# potentiometer.net
KiCad netlist of a schematic drawn in EAGLE
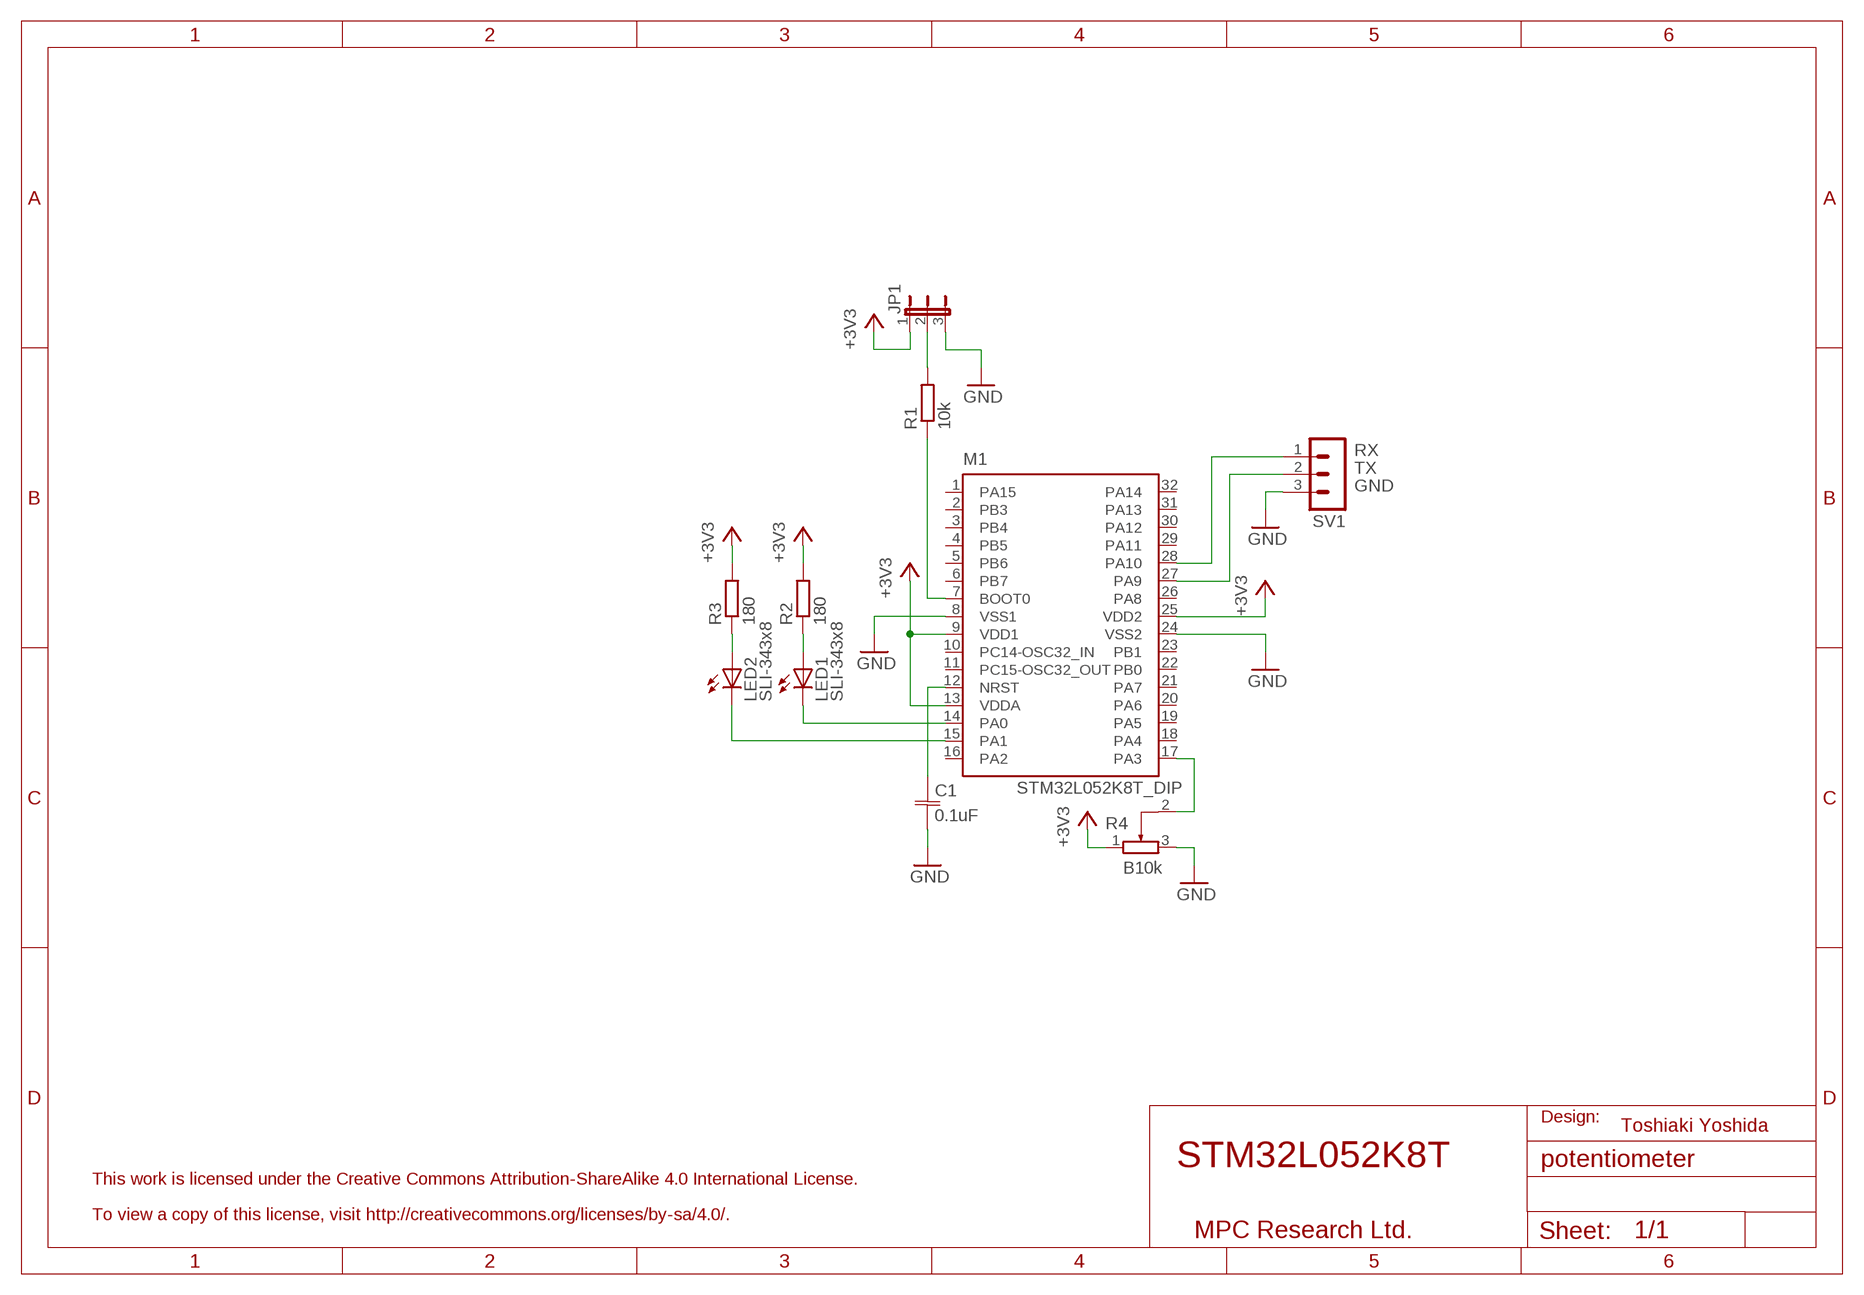
[diagram p0: schematic, sheet 1]

(export (version "E")
  (design (tool "Eeschema 10.0.6"))
  (components
    (comp (ref "C1")
      (value "0.1uF")
      (footprint "eagle-import:C050-024X044")
      (libsource (lib "eagle-import") (part "C-JIS050-024X044"))
    )
    (comp (ref "JP1")
      (value "JP2E")
      (footprint "eagle-import:JP2")
      (libsource (lib "eagle-import") (part "JP2E"))
    )
    (comp (ref "LED1")
      (value "SLI-343x8")
      (footprint "eagle-import:LED3MM")
      (libsource (lib "eagle-import") (part "LED3MM"))
    )
    (comp (ref "LED2")
      (value "SLI-343x8")
      (footprint "eagle-import:LED3MM")
      (libsource (lib "eagle-import") (part "LED3MM"))
    )
    (comp (ref "M1")
      (value "STM32L052K8T_DIP")
      (footprint "eagle-import:DIP32")
      (libsource (lib "eagle-import") (part "STM32L052K8T_DIP"))
    )
    (comp (ref "R1")
      (value "10k")
      (footprint "eagle-import:0207_2V")
      (libsource (lib "eagle-import") (part "R-EU_0207/2V"))
    )
    (comp (ref "R2")
      (value "180")
      (footprint "eagle-import:0207_2V")
      (libsource (lib "eagle-import") (part "R-EU_0207/2V"))
    )
    (comp (ref "R3")
      (value "180")
      (footprint "eagle-import:0207_2V")
      (libsource (lib "eagle-import") (part "R-EU_0207/2V"))
    )
    (comp (ref "R4")
      (value "B10k")
      (footprint "eagle-import:RK09L1140")
      (libsource (lib "eagle-import") (part "RK09L1140"))
    )
    (comp (ref "SV1")
      (value "MA03-1")
      (footprint "eagle-import:MA03-1")
      (libsource (lib "eagle-import") (part "MA03-1"))
    )
  )
  (nets
    (net (code "1") (name "+3V3") (class "Default")
      (node (ref "JP1") (pin "1") (pinfunction "1_1") (pintype "passive"))
      (node (ref "M1") (pin "13") (pinfunction "VDDA_13") (pintype "power_in"))
      (node (ref "M1") (pin "25") (pinfunction "VDD2_25") (pintype "bidirectional"))
      (node (ref "M1") (pin "9") (pinfunction "VDD1_9") (pintype "power_in"))
      (node (ref "R2") (pin "2") (pinfunction "2_2") (pintype "passive"))
      (node (ref "R3") (pin "2") (pinfunction "2_2") (pintype "passive"))
      (node (ref "R4") (pin "1") (pinfunction "1_1") (pintype "passive"))
    )
    (net (code "2") (name "GND") (class "Default")
      (node (ref "C1") (pin "2") (pinfunction "2_2") (pintype "passive"))
      (node (ref "JP1") (pin "3") (pinfunction "3_3") (pintype "passive"))
      (node (ref "M1") (pin "24") (pinfunction "VSS2_24") (pintype "power_in"))
      (node (ref "M1") (pin "8") (pinfunction "VSS1_8") (pintype "power_in"))
      (node (ref "R4") (pin "3") (pinfunction "3_3") (pintype "passive"))
      (node (ref "SV1") (pin "3") (pinfunction "3_3") (pintype "passive"))
    )
    (net (code "3") (name "Net-(JP1-Pad2)") (class "Default")
      (node (ref "JP1") (pin "2") (pinfunction "2_2") (pintype "passive"))
      (node (ref "R1") (pin "2") (pinfunction "2_2") (pintype "passive"))
    )
    (net (code "4") (name "Net-(LED1-C)") (class "Default")
      (node (ref "LED1") (pin "K") (pinfunction "C_K") (pintype "passive"))
      (node (ref "M1") (pin "14") (pinfunction "PA0_14") (pintype "bidirectional"))
    )
    (net (code "5") (name "Net-(LED1-PadA)") (class "Default")
      (node (ref "LED1") (pin "A") (pinfunction "A_A") (pintype "passive"))
      (node (ref "R2") (pin "1") (pinfunction "1_1") (pintype "passive"))
    )
    (net (code "6") (name "Net-(LED2-C)") (class "Default")
      (node (ref "LED2") (pin "K") (pinfunction "C_K") (pintype "passive"))
      (node (ref "M1") (pin "15") (pinfunction "PA1_15") (pintype "bidirectional"))
    )
    (net (code "7") (name "Net-(LED2-PadA)") (class "Default")
      (node (ref "LED2") (pin "A") (pinfunction "A_A") (pintype "passive"))
      (node (ref "R3") (pin "1") (pinfunction "1_1") (pintype "passive"))
    )
    (net (code "8") (name "Net-(M1-BOOT0)") (class "Default")
      (node (ref "M1") (pin "7") (pinfunction "BOOT0_7") (pintype "bidirectional"))
      (node (ref "R1") (pin "1") (pinfunction "1_1") (pintype "passive"))
    )
    (net (code "9") (name "Net-(M1-NRST)") (class "Default")
      (node (ref "C1") (pin "1") (pinfunction "1_1") (pintype "passive"))
      (node (ref "M1") (pin "12") (pinfunction "NRST_12") (pintype "bidirectional"))
    )
    (net (code "10") (name "Net-(M1-PA3)") (class "Default")
      (node (ref "M1") (pin "17") (pinfunction "PA3_17") (pintype "bidirectional"))
      (node (ref "R4") (pin "2") (pinfunction "2_2") (pintype "passive"))
    )
    (net (code "11") (name "Net-(M1-PA9)") (class "Default")
      (node (ref "M1") (pin "27") (pinfunction "PA9_27") (pintype "bidirectional"))
      (node (ref "SV1") (pin "2") (pinfunction "2_2") (pintype "passive"))
    )
    (net (code "12") (name "Net-(M1-PA10)") (class "Default")
      (node (ref "M1") (pin "28") (pinfunction "PA10_28") (pintype "bidirectional"))
      (node (ref "SV1") (pin "1") (pinfunction "1_1") (pintype "passive"))
    )
    (net (code "13") (name "unconnected-(M1-PA2-Pad16)") (class "Default")
      (node (ref "M1") (pin "16") (pinfunction "PA2_16") (pintype "bidirectional"))
    )
    (net (code "14") (name "unconnected-(M1-PA4-Pad18)") (class "Default")
      (node (ref "M1") (pin "18") (pinfunction "PA4_18") (pintype "bidirectional"))
    )
    (net (code "15") (name "unconnected-(M1-PA5-Pad19)") (class "Default")
      (node (ref "M1") (pin "19") (pinfunction "PA5_19") (pintype "bidirectional"))
    )
    (net (code "16") (name "unconnected-(M1-PA6-Pad20)") (class "Default")
      (node (ref "M1") (pin "20") (pinfunction "PA6_20") (pintype "bidirectional"))
    )
    (net (code "17") (name "unconnected-(M1-PA7-Pad21)") (class "Default")
      (node (ref "M1") (pin "21") (pinfunction "PA7_21") (pintype "bidirectional"))
    )
    (net (code "18") (name "unconnected-(M1-PA8-Pad26)") (class "Default")
      (node (ref "M1") (pin "26") (pinfunction "PA8_26") (pintype "bidirectional"))
    )
    (net (code "19") (name "unconnected-(M1-PA11-Pad29)") (class "Default")
      (node (ref "M1") (pin "29") (pinfunction "PA11_29") (pintype "bidirectional"))
    )
    (net (code "20") (name "unconnected-(M1-PA12-Pad30)") (class "Default")
      (node (ref "M1") (pin "30") (pinfunction "PA12_30") (pintype "bidirectional"))
    )
    (net (code "21") (name "unconnected-(M1-PA13-Pad31)") (class "Default")
      (node (ref "M1") (pin "31") (pinfunction "PA13_31") (pintype "bidirectional"))
    )
    (net (code "22") (name "unconnected-(M1-PA14-Pad32)") (class "Default")
      (node (ref "M1") (pin "32") (pinfunction "PA14_32") (pintype "bidirectional"))
    )
    (net (code "23") (name "unconnected-(M1-PA15-Pad1)") (class "Default")
      (node (ref "M1") (pin "1") (pinfunction "PA15_1") (pintype "bidirectional"))
    )
    (net (code "24") (name "unconnected-(M1-PB0-Pad22)") (class "Default")
      (node (ref "M1") (pin "22") (pinfunction "PB0_22") (pintype "bidirectional"))
    )
    (net (code "25") (name "unconnected-(M1-PB1-Pad23)") (class "Default")
      (node (ref "M1") (pin "23") (pinfunction "PB1_23") (pintype "bidirectional"))
    )
    (net (code "26") (name "unconnected-(M1-PB3-Pad2)") (class "Default")
      (node (ref "M1") (pin "2") (pinfunction "PB3_2") (pintype "bidirectional"))
    )
    (net (code "27") (name "unconnected-(M1-PB4-Pad3)") (class "Default")
      (node (ref "M1") (pin "3") (pinfunction "PB4_3") (pintype "bidirectional"))
    )
    (net (code "28") (name "unconnected-(M1-PB5-Pad4)") (class "Default")
      (node (ref "M1") (pin "4") (pinfunction "PB5_4") (pintype "bidirectional"))
    )
    (net (code "29") (name "unconnected-(M1-PB6-Pad5)") (class "Default")
      (node (ref "M1") (pin "5") (pinfunction "PB6_5") (pintype "bidirectional"))
    )
    (net (code "30") (name "unconnected-(M1-PB7-Pad6)") (class "Default")
      (node (ref "M1") (pin "6") (pinfunction "PB7_6") (pintype "bidirectional"))
    )
    (net (code "31") (name "unconnected-(M1-PC14-OSC32_IN-Pad10)") (class "Default")
      (node (ref "M1") (pin "10") (pinfunction "PC14-OSC32_IN_10") (pintype "bidirectional"))
    )
    (net (code "32") (name "unconnected-(M1-PC15-OSC32_OUT-Pad11)") (class "Default")
      (node (ref "M1") (pin "11") (pinfunction "PC15-OSC32_OUT_11") (pintype "bidirectional"))
    )
  )
)
